# ProPrj_FlightComputerV1_2026-02-14.net
KiCad netlist of a schematic drawn in EasyEDA Pro
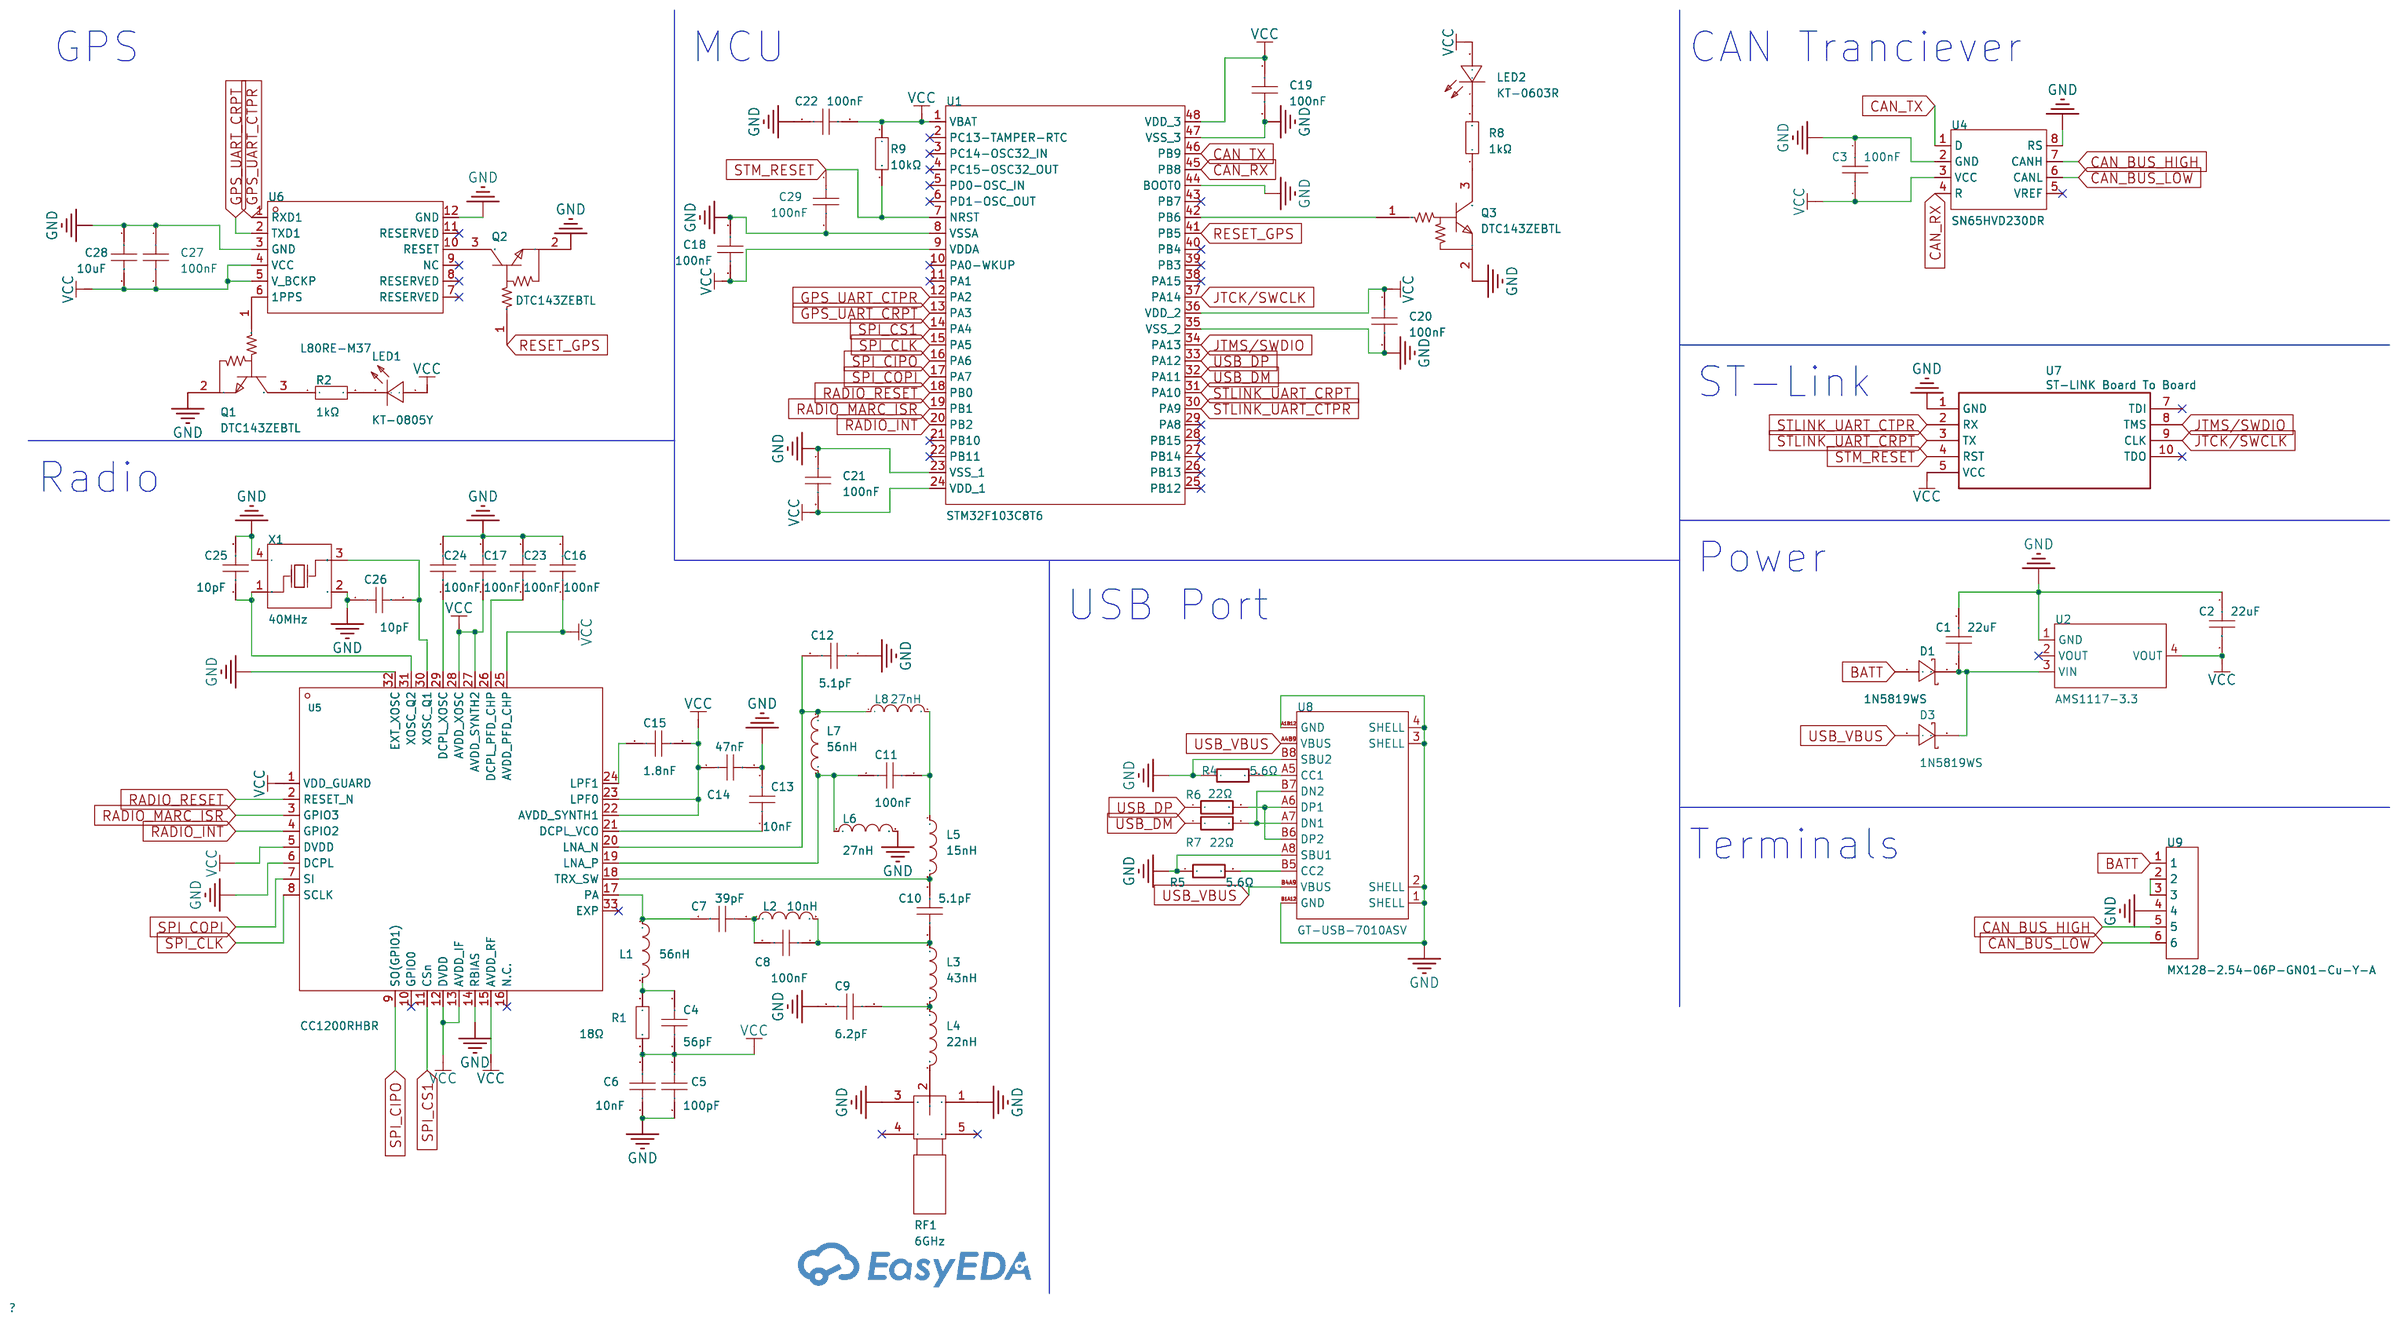
[diagram p0: schematic sheet]

(export (version "E")
  (design (tool "Eeschema 10.0.6"))
  (components
    (comp (ref "C1")
      (value "22uF")
      (footprint "easyedapro:C0805")
      (description "Capacitance:22uF Tolerance:±20% Tolerance:±20% Voltage Rating:25V Temperature Coefficient:X5R")
      (fields
        (field (name "Manufacturer Part") "CL21A226MAQNNNE")
        (field (name "Manufacturer") "SAMSUNG(三星)")
      )
      (libsource (lib "easyedapro") (part "CL21A226MAQNNNE"))
    )
    (comp (ref "C2")
      (value "22uF")
      (footprint "easyedapro:C0805")
      (description "Capacitance:22uF Tolerance:±20% Tolerance:±20% Voltage Rating:25V Temperature Coefficient:X5R")
      (fields
        (field (name "Manufacturer Part") "CL21A226MAQNNNE")
        (field (name "Manufacturer") "SAMSUNG(三星)")
      )
      (libsource (lib "easyedapro") (part "CL21A226MAQNNNE"))
    )
    (comp (ref "C3")
      (value "100nF")
      (footprint "easyedapro:C0805")
      (description "Capacitance:100nF Tolerance:±20% Tolerance:±20% Voltage Rating:25V Temperature Coefficient:X5R")
      (fields
        (field (name "Manufacturer Part") "TCC0402X5R104M250AT")
        (field (name "Manufacturer") "CCTC(三环)")
      )
      (libsource (lib "easyedapro") (part "CL21A226MAQNNNE"))
    )
    (comp (ref "C4")
      (value "56pF")
      (footprint "easyedapro:C0603")
      (description "Capacitance:56pF Tolerance:±5% Tolerance:±5% Voltage Rating:50V Temperature Coefficient:C0G")
      (fields
        (field (name "Manufacturer Part") "TCC0402COG560J500AT")
        (field (name "Manufacturer") "CCTC(三环)")
      )
      (libsource (lib "easyedapro") (part "CAP"))
    )
    (comp (ref "C5")
      (value "100pF")
      (footprint "easyedapro:C0603")
      (description "Capacitance:100pF Tolerance:±10% Tolerance:±10% Voltage Rating:50V Temperature Coefficient:C0G")
      (fields
        (field (name "Manufacturer Part") "TCC0402COG101K500AT")
        (field (name "Manufacturer") "CCTC(三环)")
      )
      (libsource (lib "easyedapro") (part "CAP"))
    )
    (comp (ref "C6")
      (value "10nF")
      (footprint "easyedapro:C0603")
      (description "Capacitance:10nF Tolerance:±20% Tolerance:±20% Voltage Rating:50V Temperature Coefficient:X7R")
      (fields
        (field (name "Manufacturer Part") "TCC0402X7R103M500AT")
        (field (name "Manufacturer") "CCTC(三环)")
      )
      (libsource (lib "easyedapro") (part "CAP"))
    )
    (comp (ref "C7")
      (value "39pF")
      (footprint "easyedapro:C0603")
      (description "Capacitance:39pF Tolerance:±5% Tolerance:±5% Voltage Rating:50V Temperature Coefficient:C0G")
      (fields
        (field (name "Manufacturer Part") "TCC0402COG390J500AT")
        (field (name "Manufacturer") "CCTC(三环)")
      )
      (libsource (lib "easyedapro") (part "CAP"))
    )
    (comp (ref "C8")
      (value "100nF")
      (footprint "easyedapro:C0603")
      (description "Capacitance:100nF Tolerance:±20% Tolerance:±20% Voltage Rating:25V Temperature Coefficient:X5R")
      (fields
        (field (name "Manufacturer Part") "TCC0402X5R104M250AT")
        (field (name "Manufacturer") "CCTC(三环)")
      )
      (libsource (lib "easyedapro") (part "CAP"))
    )
    (comp (ref "C9")
      (value "6.2pF")
      (footprint "easyedapro:C0603")
      (description "Capacitance:6.2pF Voltage Rating:50V Temperature Coefficient:C0G")
      (fields (field (name "Manufacturer Part") "0402CG6R2C500NT") (field (name "Manufacturer") "FH(风华)"))
      (libsource (lib "easyedapro") (part "CAP"))
    )
    (comp (ref "C10")
      (value "5.1pF")
      (footprint "easyedapro:C0603")
      (description "Capacitance:5.1pF Voltage Rating:50V Temperature Coefficient:C0G")
      (fields (field (name "Manufacturer Part") "0402CG5R1C500NT") (field (name "Manufacturer") "FH(风华)"))
      (libsource (lib "easyedapro") (part "CAP"))
    )
    (comp (ref "C11")
      (value "100nF")
      (footprint "easyedapro:C0603")
      (description "Capacitance:100nF Tolerance:±20% Tolerance:±20% Voltage Rating:25V Temperature Coefficient:X5R")
      (fields
        (field (name "Manufacturer Part") "TCC0402X5R104M250AT")
        (field (name "Manufacturer") "CCTC(三环)")
      )
      (libsource (lib "easyedapro") (part "CAP"))
    )
    (comp (ref "C12")
      (value "5.1pF")
      (footprint "easyedapro:C0603")
      (description "Capacitance:5.1pF Voltage Rating:50V Temperature Coefficient:C0G")
      (fields (field (name "Manufacturer Part") "0402CG5R1C500NT") (field (name "Manufacturer") "FH(风华)"))
      (libsource (lib "easyedapro") (part "CAP"))
    )
    (comp (ref "C13")
      (value "10nF")
      (footprint "easyedapro:C0603")
      (description "Capacitance:10nF Tolerance:±20% Tolerance:±20% Voltage Rating:50V Temperature Coefficient:X7R")
      (fields
        (field (name "Manufacturer Part") "TCC0402X7R103M500AT")
        (field (name "Manufacturer") "CCTC(三环)")
      )
      (libsource (lib "easyedapro") (part "CAP"))
    )
    (comp (ref "C14")
      (value "47nF")
      (footprint "easyedapro:C0603")
      (description "Capacitance:47nF Tolerance:±20% Tolerance:±20% Voltage Rating:25V Temperature Coefficient:X5R")
      (fields
        (field (name "Manufacturer Part") "TCC0402X5R473M250AT")
        (field (name "Manufacturer") "CCTC(三环)")
      )
      (libsource (lib "easyedapro") (part "CAP"))
    )
    (comp (ref "C15")
      (value "1.8nF")
      (footprint "easyedapro:C0603")
      (description "Capacitance:1.8nF Tolerance:±10% Tolerance:±10% Voltage Rating:50V Temperature Coefficient:X7R")
      (fields
        (field (name "Manufacturer Part") "TCC0402X7R182K500AT")
        (field (name "Manufacturer") "CCTC(三环)")
      )
      (libsource (lib "easyedapro") (part "CAP"))
    )
    (comp (ref "C16")
      (value "100nF")
      (footprint "easyedapro:C0805")
      (description "Capacitance:100nF Tolerance:±20% Tolerance:±20% Voltage Rating:25V Temperature Coefficient:X5R")
      (fields
        (field (name "Manufacturer Part") "TCC0402X5R104M250AT")
        (field (name "Manufacturer") "CCTC(三环)")
      )
      (libsource (lib "easyedapro") (part "CL21A226MAQNNNE"))
    )
    (comp (ref "C17")
      (value "100nF")
      (footprint "easyedapro:C0805")
      (description "Capacitance:100nF Tolerance:±20% Tolerance:±20% Voltage Rating:25V Temperature Coefficient:X5R")
      (fields
        (field (name "Manufacturer Part") "TCC0402X5R104M250AT")
        (field (name "Manufacturer") "CCTC(三环)")
      )
      (libsource (lib "easyedapro") (part "CL21A226MAQNNNE"))
    )
    (comp (ref "C18")
      (value "100nF")
      (footprint "easyedapro:C0805")
      (description "Capacitance:100nF Tolerance:±20% Tolerance:±20% Voltage Rating:25V Temperature Coefficient:X5R")
      (fields
        (field (name "Manufacturer Part") "TCC0402X5R104M250AT")
        (field (name "Manufacturer") "CCTC(三环)")
      )
      (libsource (lib "easyedapro") (part "CL21A226MAQNNNE"))
    )
    (comp (ref "C19")
      (value "100nF")
      (footprint "easyedapro:C0805")
      (description "Capacitance:100nF Tolerance:±20% Tolerance:±20% Voltage Rating:25V Temperature Coefficient:X5R")
      (fields
        (field (name "Manufacturer Part") "TCC0402X5R104M250AT")
        (field (name "Manufacturer") "CCTC(三环)")
      )
      (libsource (lib "easyedapro") (part "CL21A226MAQNNNE"))
    )
    (comp (ref "C20")
      (value "100nF")
      (footprint "easyedapro:C0805")
      (description "Capacitance:100nF Tolerance:±20% Tolerance:±20% Voltage Rating:25V Temperature Coefficient:X5R")
      (fields
        (field (name "Manufacturer Part") "TCC0402X5R104M250AT")
        (field (name "Manufacturer") "CCTC(三环)")
      )
      (libsource (lib "easyedapro") (part "CL21A226MAQNNNE"))
    )
    (comp (ref "C21")
      (value "100nF")
      (footprint "easyedapro:C0805")
      (description "Capacitance:100nF Tolerance:±20% Tolerance:±20% Voltage Rating:25V Temperature Coefficient:X5R")
      (fields
        (field (name "Manufacturer Part") "TCC0402X5R104M250AT")
        (field (name "Manufacturer") "CCTC(三环)")
      )
      (libsource (lib "easyedapro") (part "CL21A226MAQNNNE"))
    )
    (comp (ref "C22")
      (value "100nF")
      (footprint "easyedapro:C0805")
      (description "Capacitance:100nF Tolerance:±20% Tolerance:±20% Voltage Rating:25V Temperature Coefficient:X5R")
      (fields
        (field (name "Manufacturer Part") "TCC0402X5R104M250AT")
        (field (name "Manufacturer") "CCTC(三环)")
      )
      (libsource (lib "easyedapro") (part "CL21A226MAQNNNE"))
    )
    (comp (ref "C23")
      (value "100nF")
      (footprint "easyedapro:C0805")
      (description "Capacitance:100nF Tolerance:±20% Tolerance:±20% Voltage Rating:25V Temperature Coefficient:X5R")
      (fields
        (field (name "Manufacturer Part") "TCC0402X5R104M250AT")
        (field (name "Manufacturer") "CCTC(三环)")
      )
      (libsource (lib "easyedapro") (part "CL21A226MAQNNNE"))
    )
    (comp (ref "C24")
      (value "100nF")
      (footprint "easyedapro:C0805")
      (description "Capacitance:100nF Tolerance:±20% Tolerance:±20% Voltage Rating:25V Temperature Coefficient:X5R")
      (fields
        (field (name "Manufacturer Part") "TCC0402X5R104M250AT")
        (field (name "Manufacturer") "CCTC(三环)")
      )
      (libsource (lib "easyedapro") (part "CL21A226MAQNNNE"))
    )
    (comp (ref "C25")
      (value "10pF")
      (footprint "easyedapro:C0603")
      (description "Capacitance:10pF Tolerance:±10% Tolerance:±10% Voltage Rating:50V Temperature Coefficient:C0G")
      (fields
        (field (name "Manufacturer Part") "TCC0402COG100K500AT")
        (field (name "Manufacturer") "CCTC(三环)")
      )
      (libsource (lib "easyedapro") (part "CAP"))
    )
    (comp (ref "C26")
      (value "10pF")
      (footprint "easyedapro:C0603")
      (description "Capacitance:10pF Tolerance:±10% Tolerance:±10% Voltage Rating:50V Temperature Coefficient:C0G")
      (fields
        (field (name "Manufacturer Part") "TCC0402COG100K500AT")
        (field (name "Manufacturer") "CCTC(三环)")
      )
      (libsource (lib "easyedapro") (part "CAP"))
    )
    (comp (ref "C27")
      (value "100nF")
      (footprint "easyedapro:C0603")
      (description "Capacitance:100nF Tolerance:±20% Tolerance:±20% Voltage Rating:25V Temperature Coefficient:X5R")
      (fields
        (field (name "Manufacturer Part") "TCC0402X5R104M250AT")
        (field (name "Manufacturer") "CCTC(三环)")
      )
      (libsource (lib "easyedapro") (part "CAP"))
    )
    (comp (ref "C28")
      (value "10uF")
      (footprint "easyedapro:C0603")
      (description "Capacitance:10uF Tolerance:±20% Tolerance:±20% Voltage Rating:6.3V Temperature Coefficient:X5R")
      (fields
        (field (name "Manufacturer Part") "CL10A106MQ8NNNC")
        (field (name "Manufacturer") "SAMSUNG(三星)")
      )
      (libsource (lib "easyedapro") (part "CAP"))
    )
    (comp (ref "C29")
      (value "100nF")
      (footprint "easyedapro:C0805")
      (description "Capacitance:100nF Tolerance:±20% Tolerance:±20% Voltage Rating:25V Temperature Coefficient:X5R")
      (fields
        (field (name "Manufacturer Part") "TCC0402X5R104M250AT")
        (field (name "Manufacturer") "CCTC(三环)")
      )
      (libsource (lib "easyedapro") (part "CL21A226MAQNNNE"))
    )
    (comp (ref "D1")
      (value "1N5819WS")
      (footprint "easyedapro:SOD-323_L1.8-W1.3-LS2.5-RD")
      (fields (field (name "Manufacturer") "Hottech(合科泰)"))
      (libsource (lib "easyedapro") (part "1N5819WS"))
    )
    (comp (ref "D3")
      (value "1N5819WS")
      (footprint "easyedapro:SOD-323_L1.8-W1.3-LS2.5-RD")
      (fields (field (name "Manufacturer") "Hottech(合科泰)"))
      (libsource (lib "easyedapro") (part "1N5819WS"))
    )
    (comp (ref "L1")
      (value "56nH")
      (footprint "easyedapro:L0603")
      (fields (field (name "Manufacturer Part") "MLG1005S56NJT000") (field (name "Manufacturer") "TDK"))
      (libsource (lib "easyedapro") (part "电感"))
    )
    (comp (ref "L2")
      (value "10nH")
      (footprint "easyedapro:L0603")
      (fields (field (name "Manufacturer Part") "VHF100505H10NJT") (field (name "Manufacturer") "FH(风华)"))
      (libsource (lib "easyedapro") (part "电感"))
    )
    (comp (ref "L3")
      (value "43nH")
      (footprint "easyedapro:L0603")
      (fields (field (name "Manufacturer Part") "VHF100505HQ43NJT") (field (name "Manufacturer") "FH(风华)"))
      (libsource (lib "easyedapro") (part "电感"))
    )
    (comp (ref "L4")
      (value "22nH")
      (footprint "easyedapro:L0603")
      (fields (field (name "Manufacturer Part") "VHF100505HQ22NJT") (field (name "Manufacturer") "FH(风华)"))
      (libsource (lib "easyedapro") (part "电感"))
    )
    (comp (ref "L5")
      (value "15nH")
      (footprint "easyedapro:L0603")
      (fields (field (name "Manufacturer Part") "VHF100505H15NKT") (field (name "Manufacturer") "FH(风华)"))
      (libsource (lib "easyedapro") (part "电感"))
    )
    (comp (ref "L6")
      (value "27nH")
      (footprint "easyedapro:L0603")
      (fields (field (name "Manufacturer Part") "LQG15HS27NJ02D") (field (name "Manufacturer") "muRata(村田)"))
      (libsource (lib "easyedapro") (part "电感"))
    )
    (comp (ref "L7")
      (value "56nH")
      (footprint "easyedapro:L0603")
      (fields (field (name "Manufacturer Part") "MLG1005S56NJT000") (field (name "Manufacturer") "TDK"))
      (libsource (lib "easyedapro") (part "电感"))
    )
    (comp (ref "L8")
      (value "27nH")
      (footprint "easyedapro:L0603")
      (fields (field (name "Manufacturer Part") "LQG15HS27NJ02D") (field (name "Manufacturer") "muRata(村田)"))
      (libsource (lib "easyedapro") (part "电感"))
    )
    (comp (ref "LED1")
      (value "KT-0805Y")
      (footprint "easyedapro:LED0805-R-RD")
      (fields (field (name "Manufacturer") "KENTO"))
      (libsource (lib "easyedapro") (part "17-21SUYC/TR8"))
    )
    (comp (ref "LED2")
      (value "KT-0603R")
      (footprint "easyedapro:LED0603-RD")
      (fields (field (name "Manufacturer") "KENTO"))
      (libsource (lib "easyedapro") (part "KT-0603R"))
    )
    (comp (ref "Q1")
      (value "DTC143ZEBTL")
      (footprint "easyedapro:SC-89-3_L1.6-W0.9-P1.00-LS1.6-BR")
      (fields (field (name "Manufacturer") "ROHM(罗姆)"))
      (libsource (lib "easyedapro") (part "DTC143ZEBTL"))
    )
    (comp (ref "Q2")
      (value "DTC143ZEBTL")
      (footprint "easyedapro:SC-89-3_L1.6-W0.9-P1.00-LS1.6-BR")
      (fields (field (name "Manufacturer") "ROHM(罗姆)"))
      (libsource (lib "easyedapro") (part "DTC143ZEBTL"))
    )
    (comp (ref "Q3")
      (value "DTC143ZEBTL")
      (footprint "easyedapro:SC-89-3_L1.6-W0.9-P1.00-LS1.6-BR")
      (fields (field (name "Manufacturer") "ROHM(罗姆)"))
      (libsource (lib "easyedapro") (part "DTC143ZEBTL"))
    )
    (comp (ref "R1")
      (value "18Ω")
      (footprint "easyedapro:R0603")
      (fields
        (field (name "Manufacturer Part") "0805W8F180JT5E")
        (field (name "Manufacturer") "UNI-ROYAL(厚声)")
      )
      (libsource (lib "easyedapro") (part "Res"))
    )
    (comp (ref "R2")
      (value "1kΩ")
      (footprint "easyedapro:R0603")
      (fields
        (field (name "Manufacturer Part") "1206W4J0102T5E")
        (field (name "Manufacturer") "UNI-ROYAL(厚声)")
      )
      (libsource (lib "easyedapro") (part "Res"))
    )
    (comp (ref "R4")
      (value "5.6Ω")
      (fields
        (field (name "Manufacturer Part") "0603WAF5601T5E")
        (field (name "Manufacturer") "UNI-ROYAL(厚声)")
      )
      (libsource (lib "easyedapro") (part "5.6kΩ"))
    )
    (comp (ref "R5")
      (value "5.6Ω")
      (fields
        (field (name "Manufacturer Part") "0603WAF5601T5E")
        (field (name "Manufacturer") "UNI-ROYAL(厚声)")
      )
      (libsource (lib "easyedapro") (part "5.6kΩ"))
    )
    (comp (ref "R6")
      (value "22Ω")
      (fields
        (field (name "Manufacturer Part") "0603WAF5601T5E")
        (field (name "Manufacturer") "UNI-ROYAL(厚声)")
      )
      (libsource (lib "easyedapro") (part "5.6kΩ"))
    )
    (comp (ref "R7")
      (value "22Ω")
      (fields
        (field (name "Manufacturer Part") "0603WAF5601T5E")
        (field (name "Manufacturer") "UNI-ROYAL(厚声)")
      )
      (libsource (lib "easyedapro") (part "5.6kΩ"))
    )
    (comp (ref "R8")
      (value "1kΩ")
      (footprint "easyedapro:R0603")
      (fields
        (field (name "Manufacturer Part") "1206W4J0102T5E")
        (field (name "Manufacturer") "UNI-ROYAL(厚声)")
      )
      (libsource (lib "easyedapro") (part "Res"))
    )
    (comp (ref "R9")
      (value "10kΩ")
      (footprint "easyedapro:R0603")
      (fields
        (field (name "Manufacturer Part") "0402WGF1002TCE")
        (field (name "Manufacturer") "UNI-ROYAL(厚声)")
      )
      (libsource (lib "easyedapro") (part "Res"))
    )
    (comp (ref "RF1")
      (value "6GHz")
      (footprint "easyedapro:SMA-SMD_HYCW12-SMAW0863-1365B")
      (fields (field (name "Manufacturer Part") "HYCW12-SMAW0863-1365B") (field (name "Manufacturer") "华宇创"))
      (libsource (lib "easyedapro") (part "HYCW12-SMAW0863-1365B"))
    )
    (comp (ref "U1")
      (value "STM32F103C8T6")
      (footprint "easyedapro:LQFP-48_L7.0-W7.0-P0.50-LS9.0-BL")
      (fields (field (name "Manufacturer") "ST(意法半导体)"))
      (libsource (lib "easyedapro") (part "STM32F103C8T6"))
    )
    (comp (ref "U2")
      (value "AMS1117-3.3")
      (footprint "easyedapro:SOT-223-3_L6.5-W3.4-P2.30-LS7.0-BR")
      (fields (field (name "Manufacturer") "AMS"))
      (libsource (lib "easyedapro") (part "AMS1117-3.3"))
    )
    (comp (ref "U4")
      (value "SN65HVD230DR")
      (footprint "easyedapro:SOIC-8_L4.9-W3.9-P1.27-LS6.0-BL")
      (fields (field (name "Manufacturer") "TI(德州仪器)"))
      (libsource (lib "easyedapro") (part "SN65HVD230DR"))
    )
    (comp (ref "U5")
      (value "CC1200RHBR")
      (footprint "easyedapro:VQFN-32_L5.0-W5.0-P0.50-TL-EP")
      (fields (field (name "Manufacturer") "TI(德州仪器)"))
      (libsource (lib "easyedapro") (part "CC1200RHBR"))
    )
    (comp (ref "U6")
      (value "L80RE-M37")
      (footprint "easyedapro:GPSM-SMD_12P-L16.0-W16.0-P2.54-BL")
      (fields (field (name "Manufacturer") "Quectel(移远)"))
      (libsource (lib "easyedapro") (part "L80RE-M37"))
    )
    (comp (ref "U7")
      (value "ST-LINK Board To Board")
      (footprint "easyedapro:ST-LINK BOARD TO BOARD")
      (libsource (lib "easyedapro") (part "ST-LINK Board To Board"))
    )
    (comp (ref "U8")
      (value "GT-USB-7010ASV")
      (footprint "easyedapro:USB-C-SMD_G-SWITCH_GT-USB-7010ASV")
      (fields (field (name "Manufacturer") "G-Switch(品赞)"))
      (libsource (lib "easyedapro") (part "GT-USB-7010ASV"))
    )
    (comp (ref "U9")
      (value "MX128-2.54-06P-GN01-Cu-Y-A")
      (footprint "easyedapro:CONN-TH_6P-P2.54_MX128-2.54-6P")
      (fields (field (name "Manufacturer") "MAX(迈旭)"))
      (libsource (lib "easyedapro") (part "MX128-2.54-GN01-06P-CU-Y-A"))
    )
    (comp (ref "X1")
      (value "40MHz")
      (footprint "easyedapro:CRYSTAL-SMD_4P-L2.0-W1.6-BL")
      (fields (field (name "Manufacturer Part") "Q22FA12800101") (field (name "Manufacturer") "EPSON(爱普生)"))
      (libsource (lib "easyedapro") (part "Q22FA12800101"))
    )
  )
  (nets
    (net (code "1") (name "BATT") (class "Default")
      (node (ref "D1") (pin "2") (pinfunction "A_2") (pintype "unspecified"))
      (node (ref "U9") (pin "1") (pinfunction "1_1") (pintype "unspecified"))
    )
    (net (code "2") (name "CAN_BUS_HIGH") (class "Default")
      (node (ref "U4") (pin "7") (pinfunction "CANH_7") (pintype "unspecified"))
      (node (ref "U9") (pin "5") (pinfunction "5_5") (pintype "unspecified"))
    )
    (net (code "3") (name "CAN_BUS_LOW") (class "Default")
      (node (ref "U4") (pin "6") (pinfunction "CANL_6") (pintype "unspecified"))
      (node (ref "U9") (pin "6") (pinfunction "6_6") (pintype "unspecified"))
    )
    (net (code "4") (name "CAN_RX") (class "Default")
      (node (ref "U1") (pin "45") (pinfunction "PB8_45") (pintype "unspecified"))
      (node (ref "U4") (pin "4") (pinfunction "R_4") (pintype "unspecified"))
    )
    (net (code "5") (name "CAN_TX") (class "Default")
      (node (ref "U1") (pin "46") (pinfunction "PB9_46") (pintype "unspecified"))
      (node (ref "U4") (pin "1") (pinfunction "D_1") (pintype "unspecified"))
    )
    (net (code "6") (name "GND") (class "Default")
      (node (ref "C1") (pin "2") (pinfunction "2_2") (pintype "unspecified"))
      (node (ref "C12") (pin "1") (pinfunction "1_1") (pintype "input"))
      (node (ref "C13") (pin "1") (pinfunction "1_1") (pintype "input"))
      (node (ref "C14") (pin "2") (pinfunction "2_2") (pintype "input"))
      (node (ref "C16") (pin "2") (pinfunction "2_2") (pintype "unspecified"))
      (node (ref "C17") (pin "1") (pinfunction "1_1") (pintype "unspecified"))
      (node (ref "C18") (pin "1") (pinfunction "1_1") (pintype "unspecified"))
      (node (ref "C19") (pin "2") (pinfunction "2_2") (pintype "unspecified"))
      (node (ref "C2") (pin "1") (pinfunction "1_1") (pintype "unspecified"))
      (node (ref "C20") (pin "2") (pinfunction "2_2") (pintype "unspecified"))
      (node (ref "C21") (pin "1") (pinfunction "1_1") (pintype "unspecified"))
      (node (ref "C22") (pin "1") (pinfunction "1_1") (pintype "unspecified"))
      (node (ref "C23") (pin "1") (pinfunction "1_1") (pintype "unspecified"))
      (node (ref "C24") (pin "1") (pinfunction "1_1") (pintype "unspecified"))
      (node (ref "C25") (pin "2") (pinfunction "2_2") (pintype "input"))
      (node (ref "C26") (pin "1") (pinfunction "1_1") (pintype "input"))
      (node (ref "C27") (pin "1") (pinfunction "1_1") (pintype "input"))
      (node (ref "C28") (pin "1") (pinfunction "1_1") (pintype "input"))
      (node (ref "C29") (pin "2") (pinfunction "2_2") (pintype "unspecified"))
      (node (ref "C3") (pin "1") (pinfunction "1_1") (pintype "unspecified"))
      (node (ref "C5") (pin "1") (pinfunction "1_1") (pintype "input"))
      (node (ref "C6") (pin "1") (pinfunction "1_1") (pintype "input"))
      (node (ref "C9") (pin "1") (pinfunction "1_1") (pintype "input"))
      (node (ref "L6") (pin "2") (pinfunction "2_2") (pintype "input"))
      (node (ref "Q1") (pin "2") (pinfunction "E_2") (pintype "unspecified"))
      (node (ref "Q2") (pin "2") (pinfunction "E_2") (pintype "unspecified"))
      (node (ref "Q3") (pin "2") (pinfunction "E_2") (pintype "unspecified"))
      (node (ref "R4") (pin "1") (pinfunction "1_1") (pintype "input"))
      (node (ref "R5") (pin "1") (pinfunction "1_1") (pintype "input"))
      (node (ref "RF1") (pin "1") (pinfunction "1_1") (pintype "unspecified"))
      (node (ref "RF1") (pin "3") (pinfunction "3_3") (pintype "unspecified"))
      (node (ref "U1") (pin "23") (pinfunction "VSS_1_23") (pintype "unspecified"))
      (node (ref "U1") (pin "35") (pinfunction "VSS_2_35") (pintype "unspecified"))
      (node (ref "U1") (pin "44") (pinfunction "BOOT0_44") (pintype "unspecified"))
      (node (ref "U1") (pin "47") (pinfunction "VSS_3_47") (pintype "unspecified"))
      (node (ref "U1") (pin "8") (pinfunction "VSSA_8") (pintype "unspecified"))
      (node (ref "U2") (pin "1") (pinfunction "GND_1") (pintype "unspecified"))
      (node (ref "U4") (pin "2") (pinfunction "GND_2") (pintype "unspecified"))
      (node (ref "U4") (pin "8") (pinfunction "RS_8") (pintype "unspecified"))
      (node (ref "U5") (pin "14") (pinfunction "RBIAS_14") (pintype "input"))
      (node (ref "U5") (pin "32") (pinfunction "EXT_XOSC_32") (pintype "input"))
      (node (ref "U5") (pin "6") (pinfunction "DCPL_6") (pintype "input"))
      (node (ref "U6") (pin "12") (pinfunction "GND_12") (pintype "unspecified"))
      (node (ref "U6") (pin "3") (pinfunction "GND_3") (pintype "unspecified"))
      (node (ref "U7") (pin "1") (pinfunction "GND_1") (pintype "unspecified"))
      (node (ref "U8") (pin "1") (pinfunction "SHELL_1") (pintype "unspecified"))
      (node (ref "U8") (pin "2") (pinfunction "SHELL_2") (pintype "unspecified"))
      (node (ref "U8") (pin "3") (pinfunction "SHELL_3") (pintype "unspecified"))
      (node (ref "U8") (pin "4") (pinfunction "SHELL_4") (pintype "unspecified"))
      (node (ref "U8") (pin "A1B12") (pinfunction "GND_A1B12") (pintype "unspecified"))
      (node (ref "U8") (pin "A8") (pinfunction "SBU1_A8") (pintype "unspecified"))
      (node (ref "U8") (pin "B1A12") (pinfunction "GND_B1A12") (pintype "unspecified"))
      (node (ref "U8") (pin "B8") (pinfunction "SBU2_B8") (pintype "unspecified"))
      (node (ref "U9") (pin "4") (pinfunction "4_4") (pintype "unspecified"))
      (node (ref "X1") (pin "2") (pinfunction "2_2") (pintype "unspecified"))
      (node (ref "X1") (pin "4") (pinfunction "4_4") (pintype "unspecified"))
    )
    (net (code "7") (name "GPS_UART_CRPT") (class "Default")
      (node (ref "U1") (pin "13") (pinfunction "PA3_13") (pintype "unspecified"))
      (node (ref "U6") (pin "2") (pinfunction "TXD1_2") (pintype "unspecified"))
    )
    (net (code "8") (name "GPS_UART_CTPR") (class "Default")
      (node (ref "U1") (pin "12") (pinfunction "PA2_12") (pintype "unspecified"))
      (node (ref "U6") (pin "1") (pinfunction "RXD1_1") (pintype "unspecified"))
    )
    (net (code "9") (name "JTCK{slash}SWCLK") (class "Default")
      (node (ref "U1") (pin "37") (pinfunction "PA14_37") (pintype "unspecified"))
      (node (ref "U7") (pin "9") (pinfunction "CLK_9") (pintype "unspecified"))
    )
    (net (code "10") (name "JTMS{slash}SWDIO") (class "Default")
      (node (ref "U1") (pin "34") (pinfunction "PA13_34") (pintype "unspecified"))
      (node (ref "U7") (pin "8") (pinfunction "TMS_8") (pintype "unspecified"))
    )
    (net (code "11") (name "Net-(C4-Pad2)") (class "Default")
      (node (ref "C4") (pin "2") (pinfunction "2_2") (pintype "input"))
      (node (ref "L1") (pin "2") (pinfunction "2_2") (pintype "input"))
      (node (ref "R1") (pin "1") (pinfunction "1_1") (pintype "input"))
    )
    (net (code "12") (name "Net-(C7-Pad1)") (class "Default")
      (node (ref "C7") (pin "1") (pinfunction "1_1") (pintype "input"))
      (node (ref "C8") (pin "2") (pinfunction "2_2") (pintype "input"))
      (node (ref "L2") (pin "1") (pinfunction "1_1") (pintype "input"))
    )
    (net (code "13") (name "Net-(C9-Pad2)") (class "Default")
      (node (ref "C9") (pin "2") (pinfunction "2_2") (pintype "input"))
      (node (ref "L3") (pin "2") (pinfunction "2_2") (pintype "input"))
      (node (ref "L4") (pin "1") (pinfunction "1_1") (pintype "input"))
    )
    (net (code "14") (name "Net-(C10-Pad1)") (class "Default")
      (node (ref "C10") (pin "1") (pinfunction "1_1") (pintype "input"))
      (node (ref "C8") (pin "1") (pinfunction "1_1") (pintype "input"))
      (node (ref "L2") (pin "2") (pinfunction "2_2") (pintype "input"))
      (node (ref "L3") (pin "1") (pinfunction "1_1") (pintype "input"))
    )
    (net (code "15") (name "Net-(C11-Pad1)") (class "Default")
      (node (ref "C11") (pin "1") (pinfunction "1_1") (pintype "input"))
      (node (ref "L5") (pin "1") (pinfunction "1_1") (pintype "input"))
      (node (ref "L8") (pin "2") (pinfunction "2_2") (pintype "input"))
    )
    (net (code "16") (name "Net-(D1-K)") (class "Default")
      (node (ref "C1") (pin "1") (pinfunction "1_1") (pintype "unspecified"))
      (node (ref "D1") (pin "1") (pinfunction "K_1") (pintype "unspecified"))
      (node (ref "D3") (pin "1") (pinfunction "K_1") (pintype "unspecified"))
      (node (ref "U2") (pin "3") (pinfunction "VIN_3") (pintype "unspecified"))
    )
    (net (code "17") (name "Net-(L4-Pad2)") (class "Default")
      (node (ref "L4") (pin "2") (pinfunction "2_2") (pintype "input"))
      (node (ref "RF1") (pin "2") (pinfunction "2_2") (pintype "unspecified"))
    )
    (net (code "18") (name "Net-(LED1--)") (class "Default")
      (node (ref "LED1") (pin "2") (pinfunction "-_2") (pintype "unspecified"))
      (node (ref "R2") (pin "2") (pinfunction "2_2") (pintype "input"))
    )
    (net (code "19") (name "Net-(LED2-K)") (class "Default")
      (node (ref "LED2") (pin "1") (pinfunction "K_1") (pintype "unspecified"))
      (node (ref "R8") (pin "2") (pinfunction "2_2") (pintype "input"))
    )
    (net (code "20") (name "Net-(Q1-B)") (class "Default")
      (node (ref "Q1") (pin "1") (pinfunction "B_1") (pintype "unspecified"))
      (node (ref "U6") (pin "6") (pinfunction "1PPS_6") (pintype "unspecified"))
    )
    (net (code "21") (name "Net-(Q1-C)") (class "Default")
      (node (ref "Q1") (pin "3") (pinfunction "C_3") (pintype "unspecified"))
      (node (ref "R2") (pin "1") (pinfunction "1_1") (pintype "input"))
    )
    (net (code "22") (name "Net-(Q2-C)") (class "Default")
      (node (ref "Q2") (pin "3") (pinfunction "C_3") (pintype "unspecified"))
      (node (ref "U6") (pin "10") (pinfunction "RESET_10") (pintype "unspecified"))
    )
    (net (code "23") (name "Net-(Q3-B)") (class "Default")
      (node (ref "Q3") (pin "1") (pinfunction "B_1") (pintype "unspecified"))
      (node (ref "U1") (pin "42") (pinfunction "PB6_42") (pintype "unspecified"))
    )
    (net (code "24") (name "Net-(Q3-C)") (class "Default")
      (node (ref "Q3") (pin "3") (pinfunction "C_3") (pintype "unspecified"))
      (node (ref "R8") (pin "1") (pinfunction "1_1") (pintype "input"))
    )
    (net (code "25") (name "Net-(U5-DCPL_PFD_CHP)") (class "Default")
      (node (ref "C23") (pin "2") (pinfunction "2_2") (pintype "unspecified"))
      (node (ref "U5") (pin "26") (pinfunction "DCPL_PFD_CHP_26") (pintype "input"))
    )
    (net (code "26") (name "Net-(U5-DCPL_VCO)") (class "Default")
      (node (ref "C13") (pin "2") (pinfunction "2_2") (pintype "input"))
      (node (ref "U5") (pin "21") (pinfunction "DCPL_VCO_21") (pintype "input"))
    )
    (net (code "27") (name "Net-(U5-DCPL_XOSC)") (class "Default")
      (node (ref "C24") (pin "2") (pinfunction "2_2") (pintype "unspecified"))
      (node (ref "U5") (pin "29") (pinfunction "DCPL_XOSC_29") (pintype "input"))
    )
    (net (code "28") (name "Net-(U5-LNA_N)") (class "Default")
      (node (ref "C12") (pin "2") (pinfunction "2_2") (pintype "input"))
      (node (ref "L7") (pin "2") (pinfunction "2_2") (pintype "input"))
      (node (ref "L8") (pin "1") (pinfunction "1_1") (pintype "input"))
      (node (ref "U5") (pin "20") (pinfunction "LNA_N_20") (pintype "input"))
    )
    (net (code "29") (name "Net-(U5-LNA_P)") (class "Default")
      (node (ref "C11") (pin "2") (pinfunction "2_2") (pintype "input"))
      (node (ref "L6") (pin "1") (pinfunction "1_1") (pintype "input"))
      (node (ref "L7") (pin "1") (pinfunction "1_1") (pintype "input"))
      (node (ref "U5") (pin "19") (pinfunction "LNA_P_19") (pintype "input"))
    )
    (net (code "30") (name "Net-(U5-LPF1)") (class "Default")
      (node (ref "C15") (pin "1") (pinfunction "1_1") (pintype "input"))
      (node (ref "U5") (pin "24") (pinfunction "LPF1_24") (pintype "input"))
    )
    (net (code "31") (name "Net-(U5-PA)") (class "Default")
      (node (ref "C7") (pin "2") (pinfunction "2_2") (pintype "input"))
      (node (ref "L1") (pin "1") (pinfunction "1_1") (pintype "input"))
      (node (ref "U5") (pin "17") (pinfunction "PA_17") (pintype "input"))
    )
    (net (code "32") (name "Net-(U5-TRX_SW)") (class "Default")
      (node (ref "C10") (pin "2") (pinfunction "2_2") (pintype "input"))
      (node (ref "L5") (pin "2") (pinfunction "2_2") (pintype "input"))
      (node (ref "U5") (pin "18") (pinfunction "TRX_SW_18") (pintype "input"))
    )
    (net (code "33") (name "Net-(U5-XOSC_Q1)") (class "Default")
      (node (ref "C26") (pin "2") (pinfunction "2_2") (pintype "input"))
      (node (ref "U5") (pin "30") (pinfunction "XOSC_Q1_30") (pintype "input"))
      (node (ref "X1") (pin "3") (pinfunction "OSC2_3") (pintype "unspecified"))
    )
    (net (code "34") (name "Net-(U5-XOSC_Q2)") (class "Default")
      (node (ref "C25") (pin "1") (pinfunction "1_1") (pintype "input"))
      (node (ref "U5") (pin "31") (pinfunction "XOSC_Q2_31") (pintype "input"))
      (node (ref "X1") (pin "1") (pinfunction "OSC1_1") (pintype "unspecified"))
    )
    (net (code "35") (name "Net-(U8-CC1)") (class "Default")
      (node (ref "R4") (pin "2") (pinfunction "2_2") (pintype "input"))
      (node (ref "U8") (pin "A5") (pinfunction "CC1_A5") (pintype "unspecified"))
    )
    (net (code "36") (name "Net-(U8-CC2)") (class "Default")
      (node (ref "R5") (pin "2") (pinfunction "2_2") (pintype "input"))
      (node (ref "U8") (pin "B5") (pinfunction "CC2_B5") (pintype "unspecified"))
    )
    (net (code "37") (name "Net-(U8-DN1)") (class "Default")
      (node (ref "R7") (pin "2") (pinfunction "2_2") (pintype "input"))
      (node (ref "U8") (pin "A7") (pinfunction "DN1_A7") (pintype "unspecified"))
      (node (ref "U8") (pin "B7") (pinfunction "DN2_B7") (pintype "unspecified"))
    )
    (net (code "38") (name "Net-(U8-DP1)") (class "Default")
      (node (ref "R6") (pin "2") (pinfunction "2_2") (pintype "input"))
      (node (ref "U8") (pin "A6") (pinfunction "DP1_A6") (pintype "unspecified"))
      (node (ref "U8") (pin "B6") (pinfunction "DP2_B6") (pintype "unspecified"))
    )
    (net (code "39") (name "Net-(U9-Pad2)") (class "Default")
      (node (ref "U9") (pin "2") (pinfunction "2_2") (pintype "unspecified"))
      (node (ref "U9") (pin "3") (pinfunction "3_3") (pintype "unspecified"))
    )
    (net (code "40") (name "RADIO_INT") (class "Default")
      (node (ref "U1") (pin "20") (pinfunction "PB2_20") (pintype "unspecified"))
      (node (ref "U5") (pin "4") (pinfunction "GPIO2_4") (pintype "input"))
    )
    (net (code "41") (name "RADIO_MARC_ISR") (class "Default")
      (node (ref "U1") (pin "19") (pinfunction "PB1_19") (pintype "unspecified"))
      (node (ref "U5") (pin "3") (pinfunction "GPIO3_3") (pintype "input"))
    )
    (net (code "42") (name "RADIO_RESET") (class "Default")
      (node (ref "U1") (pin "18") (pinfunction "PB0_18") (pintype "unspecified"))
      (node (ref "U5") (pin "2") (pinfunction "RESET_N_2") (pintype "input"))
    )
    (net (code "43") (name "RESET_GPS") (class "Default")
      (node (ref "Q2") (pin "1") (pinfunction "B_1") (pintype "unspecified"))
      (node (ref "U1") (pin "41") (pinfunction "PB5_41") (pintype "unspecified"))
    )
    (net (code "44") (name "SPI_CIPO") (class "Default")
      (node (ref "U1") (pin "16") (pinfunction "PA6_16") (pintype "unspecified"))
      (node (ref "U5") (pin "9") (pinfunction "SO(GPIO1)_9") (pintype "input"))
    )
    (net (code "45") (name "SPI_CLK") (class "Default")
      (node (ref "U1") (pin "15") (pinfunction "PA5_15") (pintype "unspecified"))
      (node (ref "U5") (pin "8") (pinfunction "SCLK_8") (pintype "input"))
    )
    (net (code "46") (name "SPI_COPI") (class "Default")
      (node (ref "U1") (pin "17") (pinfunction "PA7_17") (pintype "unspecified"))
      (node (ref "U5") (pin "7") (pinfunction "SI_7") (pintype "input"))
    )
    (net (code "47") (name "SPI_CS1") (class "Default")
      (node (ref "U1") (pin "14") (pinfunction "PA4_14") (pintype "unspecified"))
      (node (ref "U5") (pin "11") (pinfunction "CSn_11") (pintype "input"))
    )
    (net (code "48") (name "STLINK_UART_CRPT") (class "Default")
      (node (ref "U1") (pin "31") (pinfunction "PA10_31") (pintype "unspecified"))
      (node (ref "U7") (pin "3") (pinfunction "TX_3") (pintype "unspecified"))
    )
    (net (code "49") (name "STLINK_UART_CTPR") (class "Default")
      (node (ref "U1") (pin "30") (pinfunction "PA9_30") (pintype "unspecified"))
      (node (ref "U7") (pin "2") (pinfunction "RX_2") (pintype "unspecified"))
    )
    (net (code "50") (name "STM_RESET") (class "Default")
      (node (ref "C29") (pin "1") (pinfunction "1_1") (pintype "unspecified"))
      (node (ref "R9") (pin "2") (pinfunction "2_2") (pintype "input"))
      (node (ref "U1") (pin "7") (pinfunction "NRST_7") (pintype "unspecified"))
      (node (ref "U7") (pin "4") (pinfunction "RST_4") (pintype "unspecified"))
    )
    (net (code "51") (name "USB_DM") (class "Default")
      (node (ref "R7") (pin "1") (pinfunction "1_1") (pintype "input"))
      (node (ref "U1") (pin "32") (pinfunction "PA11_32") (pintype "unspecified"))
    )
    (net (code "52") (name "USB_DP") (class "Default")
      (node (ref "R6") (pin "1") (pinfunction "1_1") (pintype "input"))
      (node (ref "U1") (pin "33") (pinfunction "PA12_33") (pintype "unspecified"))
    )
    (net (code "53") (name "USB_VBUS") (class "Default")
      (node (ref "D3") (pin "2") (pinfunction "A_2") (pintype "unspecified"))
      (node (ref "U8") (pin "A4B9") (pinfunction "VBUS_A4B9") (pintype "unspecified"))
      (node (ref "U8") (pin "B4A9") (pinfunction "VBUS_B4A9") (pintype "unspecified"))
    )
    (net (code "54") (name "VCC") (class "Default")
      (node (ref "C14") (pin "1") (pinfunction "1_1") (pintype "input"))
      (node (ref "C15") (pin "2") (pinfunction "2_2") (pintype "input"))
      (node (ref "C16") (pin "1") (pinfunction "1_1") (pintype "unspecified"))
      (node (ref "C17") (pin "2") (pinfunction "2_2") (pintype "unspecified"))
      (node (ref "C18") (pin "2") (pinfunction "2_2") (pintype "unspecified"))
      (node (ref "C19") (pin "1") (pinfunction "1_1") (pintype "unspecified"))
      (node (ref "C2") (pin "2") (pinfunction "2_2") (pintype "unspecified"))
      (node (ref "C20") (pin "1") (pinfunction "1_1") (pintype "unspecified"))
      (node (ref "C21") (pin "2") (pinfunction "2_2") (pintype "unspecified"))
      (node (ref "C22") (pin "2") (pinfunction "2_2") (pintype "unspecified"))
      (node (ref "C27") (pin "2") (pinfunction "2_2") (pintype "input"))
      (node (ref "C28") (pin "2") (pinfunction "2_2") (pintype "input"))
      (node (ref "C3") (pin "2") (pinfunction "2_2") (pintype "unspecified"))
      (node (ref "C4") (pin "1") (pinfunction "1_1") (pintype "input"))
      (node (ref "C5") (pin "2") (pinfunction "2_2") (pintype "input"))
      (node (ref "C6") (pin "2") (pinfunction "2_2") (pintype "input"))
      (node (ref "LED1") (pin "1") (pinfunction "+_1") (pintype "unspecified"))
      (node (ref "LED2") (pin "2") (pinfunction "A_2") (pintype "unspecified"))
      (node (ref "R1") (pin "2") (pinfunction "2_2") (pintype "input"))
      (node (ref "R9") (pin "1") (pinfunction "1_1") (pintype "input"))
      (node (ref "U1") (pin "1") (pinfunction "VBAT_1") (pintype "unspecified"))
      (node (ref "U1") (pin "24") (pinfunction "VDD_1_24") (pintype "unspecified"))
      (node (ref "U1") (pin "36") (pinfunction "VDD_2_36") (pintype "unspecified"))
      (node (ref "U1") (pin "48") (pinfunction "VDD_3_48") (pintype "unspecified"))
      (node (ref "U1") (pin "9") (pinfunction "VDDA_9") (pintype "unspecified"))
      (node (ref "U2") (pin "4") (pinfunction "VOUT_4") (pintype "unspecified"))
      (node (ref "U4") (pin "3") (pinfunction "VCC_3") (pintype "unspecified"))
      (node (ref "U5") (pin "1") (pinfunction "VDD_GUARD_1") (pintype "input"))
      (node (ref "U5") (pin "12") (pinfunction "DVDD_12") (pintype "input"))
      (node (ref "U5") (pin "13") (pinfunction "AVDD_IF_13") (pintype "input"))
      (node (ref "U5") (pin "15") (pinfunction "AVDD_RF_15") (pintype "input"))
      (node (ref "U5") (pin "22") (pinfunction "AVDD_SYNTH1_22") (pintype "input"))
      (node (ref "U5") (pin "23") (pinfunction "LPF0_23") (pintype "input"))
      (node (ref "U5") (pin "25") (pinfunction "AVDD_PFD_CHP_25") (pintype "input"))
      (node (ref "U5") (pin "27") (pinfunction "AVDD_SYNTH2_27") (pintype "input"))
      (node (ref "U5") (pin "28") (pinfunction "AVDD_XOSC_28") (pintype "input"))
      (node (ref "U5") (pin "5") (pinfunction "DVDD_5") (pintype "input"))
      (node (ref "U6") (pin "4") (pinfunction "VCC_4") (pintype "unspecified"))
      (node (ref "U6") (pin "5") (pinfunction "V_BCKP_5") (pintype "unspecified"))
      (node (ref "U7") (pin "5") (pinfunction "VCC_5") (pintype "unspecified"))
    )
    (net (code "55") (name "unconnected-(RF1-Pad4)") (class "Default")
      (node (ref "RF1") (pin "4") (pinfunction "4_4") (pintype "unspecified+no_connect"))
    )
    (net (code "56") (name "unconnected-(RF1-Pad5)") (class "Default")
      (node (ref "RF1") (pin "5") (pinfunction "5_5") (pintype "unspecified+no_connect"))
    )
    (net (code "57") (name "unconnected-(U1-PA0-WKUP-Pad10)") (class "Default")
      (node (ref "U1") (pin "10") (pinfunction "PA0-WKUP_10") (pintype "unspecified+no_connect"))
    )
    (net (code "58") (name "unconnected-(U1-PA1-Pad11)") (class "Default")
      (node (ref "U1") (pin "11") (pinfunction "PA1_11") (pintype "unspecified+no_connect"))
    )
    (net (code "59") (name "unconnected-(U1-PA8-Pad29)") (class "Default")
      (node (ref "U1") (pin "29") (pinfunction "PA8_29") (pintype "unspecified+no_connect"))
    )
    (net (code "60") (name "unconnected-(U1-PA15-Pad38)") (class "Default")
      (node (ref "U1") (pin "38") (pinfunction "PA15_38") (pintype "unspecified+no_connect"))
    )
    (net (code "61") (name "unconnected-(U1-PB3-Pad39)") (class "Default")
      (node (ref "U1") (pin "39") (pinfunction "PB3_39") (pintype "unspecified+no_connect"))
    )
    (net (code "62") (name "unconnected-(U1-PB4-Pad40)") (class "Default")
      (node (ref "U1") (pin "40") (pinfunction "PB4_40") (pintype "unspecified+no_connect"))
    )
    (net (code "63") (name "unconnected-(U1-PB7-Pad43)") (class "Default")
      (node (ref "U1") (pin "43") (pinfunction "PB7_43") (pintype "unspecified+no_connect"))
    )
    (net (code "64") (name "unconnected-(U1-PB10-Pad21)") (class "Default")
      (node (ref "U1") (pin "21") (pinfunction "PB10_21") (pintype "unspecified+no_connect"))
    )
    (net (code "65") (name "unconnected-(U1-PB11-Pad22)") (class "Default")
      (node (ref "U1") (pin "22") (pinfunction "PB11_22") (pintype "unspecified+no_connect"))
    )
    (net (code "66") (name "unconnected-(U1-PB12-Pad25)") (class "Default")
      (node (ref "U1") (pin "25") (pinfunction "PB12_25") (pintype "unspecified+no_connect"))
    )
    (net (code "67") (name "unconnected-(U1-PB13-Pad26)") (class "Default")
      (node (ref "U1") (pin "26") (pinfunction "PB13_26") (pintype "unspecified+no_connect"))
    )
    (net (code "68") (name "unconnected-(U1-PB14-Pad27)") (class "Default")
      (node (ref "U1") (pin "27") (pinfunction "PB14_27") (pintype "unspecified+no_connect"))
    )
    (net (code "69") (name "unconnected-(U1-PB15-Pad28)") (class "Default")
      (node (ref "U1") (pin "28") (pinfunction "PB15_28") (pintype "unspecified+no_connect"))
    )
    (net (code "70") (name "unconnected-(U1-PC13-TAMPER-RTC-Pad2)") (class "Default")
      (node (ref "U1") (pin "2") (pinfunction "PC13-TAMPER-RTC_2") (pintype "unspecified+no_connect"))
    )
    (net (code "71") (name "unconnected-(U1-PC14-OSC32_IN-Pad3)") (class "Default")
      (node (ref "U1") (pin "3") (pinfunction "PC14-OSC32_IN_3") (pintype "unspecified+no_connect"))
    )
    (net (code "72") (name "unconnected-(U1-PC15-OSC32_OUT-Pad4)") (class "Default")
      (node (ref "U1") (pin "4") (pinfunction "PC15-OSC32_OUT_4") (pintype "unspecified+no_connect"))
    )
    (net (code "73") (name "unconnected-(U1-PD0-OSC_IN-Pad5)") (class "Default")
      (node (ref "U1") (pin "5") (pinfunction "PD0-OSC_IN_5") (pintype "unspecified+no_connect"))
    )
    (net (code "74") (name "unconnected-(U1-PD1-OSC_OUT-Pad6)") (class "Default")
      (node (ref "U1") (pin "6") (pinfunction "PD1-OSC_OUT_6") (pintype "unspecified+no_connect"))
    )
    (net (code "75") (name "unconnected-(U2-VOUT-Pad2)") (class "Default")
      (node (ref "U2") (pin "2") (pinfunction "VOUT_2") (pintype "unspecified+no_connect"))
    )
    (net (code "76") (name "unconnected-(U4-VREF-Pad5)") (class "Default")
      (node (ref "U4") (pin "5") (pinfunction "VREF_5") (pintype "unspecified+no_connect"))
    )
    (net (code "77") (name "unconnected-(U5-EXP-Pad33)") (class "Default")
      (node (ref "U5") (pin "33") (pinfunction "EXP_33") (pintype "input+no_connect"))
    )
    (net (code "78") (name "unconnected-(U5-GPIO0-Pad10)") (class "Default")
      (node (ref "U5") (pin "10") (pinfunction "GPIO0_10") (pintype "input+no_connect"))
    )
    (net (code "79") (name "unconnected-(U5-N.C.-Pad16)") (class "Default")
      (node (ref "U5") (pin "16") (pinfunction "N.C._16") (pintype "input+no_connect"))
    )
    (net (code "80") (name "unconnected-(U6-NC-Pad9)") (class "Default")
      (node (ref "U6") (pin "9") (pinfunction "NC_9") (pintype "unspecified+no_connect"))
    )
    (net (code "81") (name "unconnected-(U6-RESERVED-Pad7)") (class "Default")
      (node (ref "U6") (pin "7") (pinfunction "RESERVED_7") (pintype "unspecified+no_connect"))
    )
    (net (code "82") (name "unconnected-(U6-RESERVED-Pad8)") (class "Default")
      (node (ref "U6") (pin "8") (pinfunction "RESERVED_8") (pintype "unspecified+no_connect"))
    )
    (net (code "83") (name "unconnected-(U6-RESERVED-Pad11)") (class "Default")
      (node (ref "U6") (pin "11") (pinfunction "RESERVED_11") (pintype "unspecified+no_connect"))
    )
    (net (code "84") (name "unconnected-(U7-TDI-Pad7)") (class "Default")
      (node (ref "U7") (pin "7") (pinfunction "TDI_7") (pintype "unspecified+no_connect"))
    )
    (net (code "85") (name "unconnected-(U7-TDO-Pad10)") (class "Default")
      (node (ref "U7") (pin "10") (pinfunction "TDO_10") (pintype "unspecified+no_connect"))
    )
  )
)
